# 19_-DDR4_260_PIN_CON.net
KiCad netlist of a schematic drawn in Altium Designer
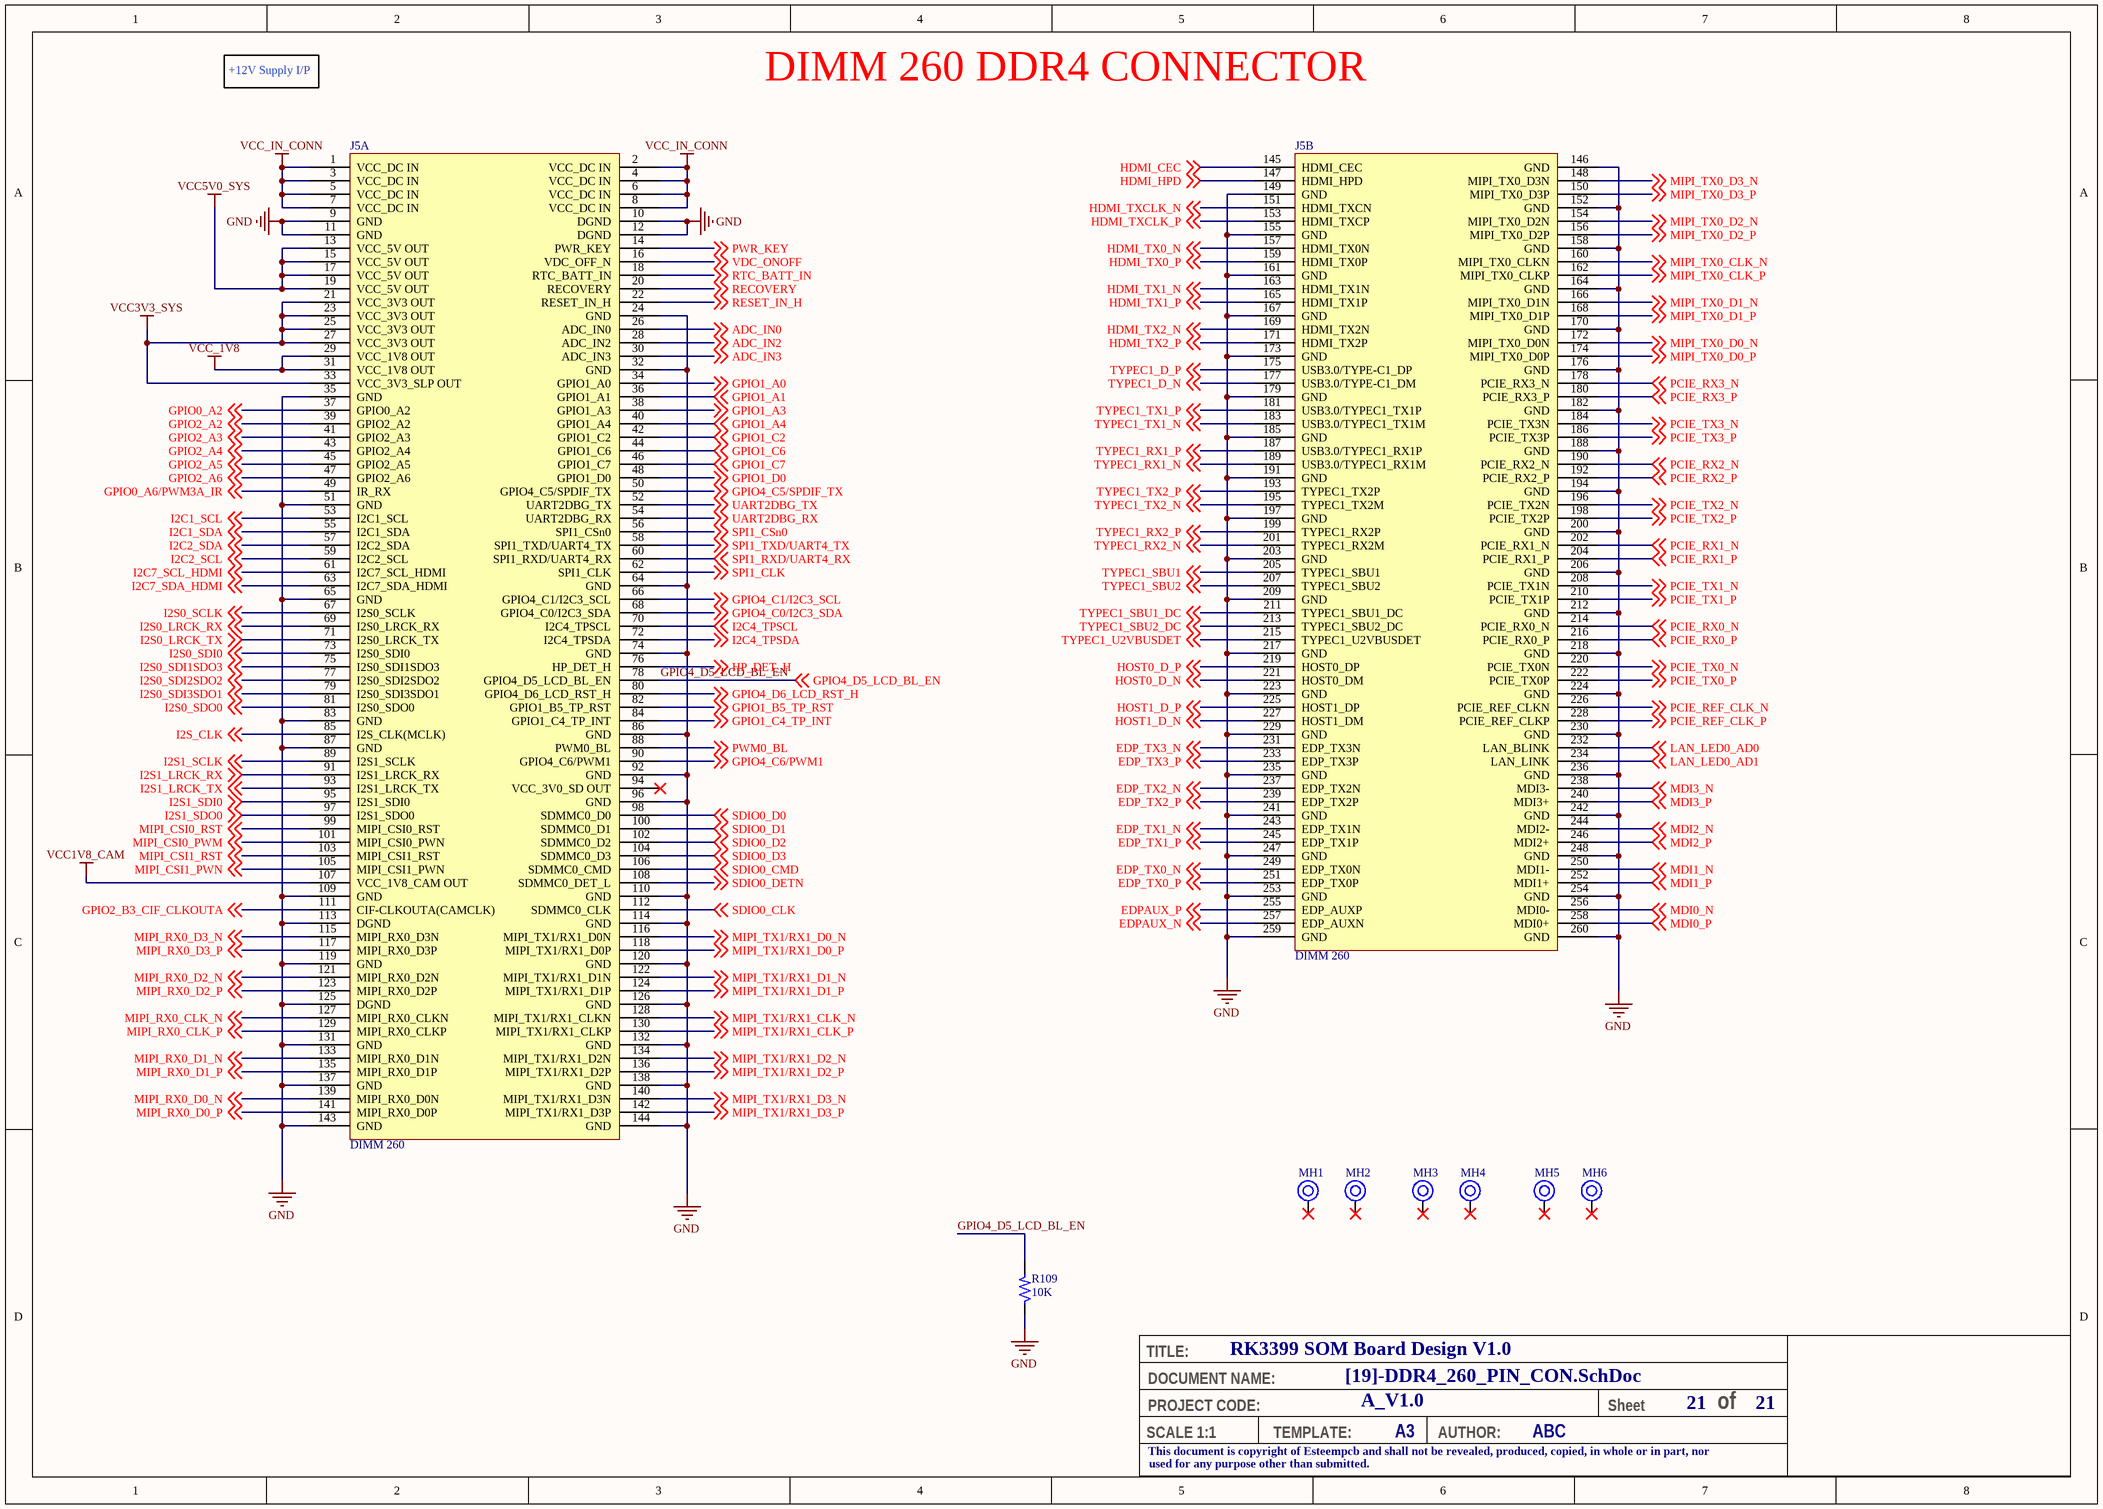
[diagram p0: [19]-DDR4_260_PIN_CON.SchDoc]

(export (version "E")
  (design (tool "Eeschema 10.0.6"))
  (components
    (comp (ref "J5")
      (value "DIMM 260")
      (footprint "DIMM260_DDR4")
      (description "Dimm 260 pin smd plating on pcb")
      (fields (field (name "MANUFACTURER") "NA"))
      (libsource (lib "RK3399 _Module_Schlib") (part "CON-DIMM_260-SMD"))
    )
    (comp (ref "MH1")
      (value "Mounting Hole")
      (footprint "SOM_Mounting")
      (fields (field (name "MANUFACTURER PART NUMBER") "NA"))
      (libsource (lib "EsteemPCB_SOM_Course_intlib") (part "MH_3.5H_6D"))
    )
    (comp (ref "MH2")
      (value "Mounting Hole")
      (footprint "SOM_Mounting")
      (fields (field (name "MANUFACTURER PART NUMBER") "NA"))
      (libsource (lib "EsteemPCB_SOM_Course_intlib") (part "MH_3.5H_6D"))
    )
    (comp (ref "MH3")
      (value "Mounting Hole")
      (footprint "SOM_Mounting")
      (fields (field (name "MANUFACTURER PART NUMBER") "NA"))
      (libsource (lib "EsteemPCB_SOM_Course_intlib") (part "MH_3.5H_6D"))
    )
    (comp (ref "MH4")
      (value "Mounting Hole")
      (footprint "SOM_Mounting")
      (fields (field (name "MANUFACTURER PART NUMBER") "NA"))
      (libsource (lib "EsteemPCB_SOM_Course_intlib") (part "MH_3.5H_6D"))
    )
    (comp (ref "MH5")
      (value "Mounting Hole")
      (footprint "SOM_Mounting")
      (fields (field (name "MANUFACTURER PART NUMBER") "NA"))
      (libsource (lib "EsteemPCB_SOM_Course_intlib") (part "MH_3.5H_6D"))
    )
    (comp (ref "MH6")
      (value "Mounting Hole")
      (footprint "SOM_Mounting")
      (fields (field (name "MANUFACTURER PART NUMBER") "NA"))
      (libsource (lib "EsteemPCB_SOM_Course_intlib") (part "MH_3.5H_6D"))
    )
    (comp (ref "R109")
      (value "10K")
      (footprint "RES_0402")
      (description "10 kOhms ±1% 0.1W, 1/10W Chip Resistor 0402 (1005 Metric) Anti-Sulfur Thin Film")
      (fields
        (field (name "MANUFACTURER") "Vishay Beyschlag/Draloric/BC Components")
        (field (name "MANUFACTURER PART NUMBER") "MCS04020C1002FE000")
      )
      (libsource (lib "RK3399 _Module_Schlib") (part "RES_10K-0.1W-1%-0402"))
    )
  )
  (nets
    (net (code "1") (name "ADC_IN0") (class "Default")
      (node (ref "J5") (pin "26") (pinfunction "ADC_IN0_26") (pintype "passive"))
    )
    (net (code "2") (name "ADC_IN2") (class "Default")
      (node (ref "J5") (pin "28") (pinfunction "ADC_IN2_28") (pintype "passive"))
    )
    (net (code "3") (name "ADC_IN3") (class "Default")
      (node (ref "J5") (pin "30") (pinfunction "ADC_IN3_30") (pintype "passive"))
    )
    (net (code "4") (name "EDPAUX_N") (class "Default")
      (node (ref "J5") (pin "257") (pinfunction "EDP_AUXN_257") (pintype "passive"))
    )
    (net (code "5") (name "EDPAUX_P") (class "Default")
      (node (ref "J5") (pin "255") (pinfunction "EDP_AUXP_255") (pintype "passive"))
    )
    (net (code "6") (name "EDP_TX0_N") (class "Default")
      (node (ref "J5") (pin "249") (pinfunction "EDP_TX0N_249") (pintype "passive"))
    )
    (net (code "7") (name "EDP_TX0_P") (class "Default")
      (node (ref "J5") (pin "251") (pinfunction "EDP_TX0P_251") (pintype "passive"))
    )
    (net (code "8") (name "EDP_TX1_N") (class "Default")
      (node (ref "J5") (pin "243") (pinfunction "EDP_TX1N_243") (pintype "passive"))
    )
    (net (code "9") (name "EDP_TX1_P") (class "Default")
      (node (ref "J5") (pin "245") (pinfunction "EDP_TX1P_245") (pintype "passive"))
    )
    (net (code "10") (name "EDP_TX2_N") (class "Default")
      (node (ref "J5") (pin "237") (pinfunction "EDP_TX2N_237") (pintype "passive"))
    )
    (net (code "11") (name "EDP_TX2_P") (class "Default")
      (node (ref "J5") (pin "239") (pinfunction "EDP_TX2P_239") (pintype "passive"))
    )
    (net (code "12") (name "EDP_TX3_N") (class "Default")
      (node (ref "J5") (pin "231") (pinfunction "EDP_TX3N_231") (pintype "passive"))
    )
    (net (code "13") (name "EDP_TX3_P") (class "Default")
      (node (ref "J5") (pin "233") (pinfunction "EDP_TX3P_233") (pintype "passive"))
    )
    (net (code "14") (name "GND") (class "Default")
      (node (ref "J5") (pin "10") (pinfunction "DGND_10") (pintype "passive"))
      (node (ref "J5") (pin "109") (pinfunction "GND_109") (pintype "passive"))
      (node (ref "J5") (pin "11") (pinfunction "GND_11") (pintype "passive"))
      (node (ref "J5") (pin "110") (pinfunction "GND_110") (pintype "passive"))
      (node (ref "J5") (pin "113") (pinfunction "DGND_113") (pintype "passive"))
      (node (ref "J5") (pin "114") (pinfunction "GND_114") (pintype "passive"))
      (node (ref "J5") (pin "119") (pinfunction "GND_119") (pintype "passive"))
      (node (ref "J5") (pin "12") (pinfunction "DGND_12") (pintype "passive"))
      (node (ref "J5") (pin "120") (pinfunction "GND_120") (pintype "passive"))
      (node (ref "J5") (pin "125") (pinfunction "DGND_125") (pintype "passive"))
      (node (ref "J5") (pin "126") (pinfunction "GND_126") (pintype "passive"))
      (node (ref "J5") (pin "131") (pinfunction "GND_131") (pintype "passive"))
      (node (ref "J5") (pin "132") (pinfunction "GND_132") (pintype "passive"))
      (node (ref "J5") (pin "137") (pinfunction "GND_137") (pintype "passive"))
      (node (ref "J5") (pin "138") (pinfunction "GND_138") (pintype "passive"))
      (node (ref "J5") (pin "143") (pinfunction "GND_143") (pintype "passive"))
      (node (ref "J5") (pin "144") (pinfunction "GND_144") (pintype "passive"))
      (node (ref "J5") (pin "146") (pinfunction "GND_146") (pintype "passive"))
      (node (ref "J5") (pin "149") (pinfunction "GND_149") (pintype "passive"))
      (node (ref "J5") (pin "152") (pinfunction "GND_152") (pintype "passive"))
      (node (ref "J5") (pin "155") (pinfunction "GND_155") (pintype "passive"))
      (node (ref "J5") (pin "158") (pinfunction "GND_158") (pintype "passive"))
      (node (ref "J5") (pin "161") (pinfunction "GND_161") (pintype "passive"))
      (node (ref "J5") (pin "164") (pinfunction "GND_164") (pintype "passive"))
      (node (ref "J5") (pin "167") (pinfunction "GND_167") (pintype "passive"))
      (node (ref "J5") (pin "170") (pinfunction "GND_170") (pintype "passive"))
      (node (ref "J5") (pin "173") (pinfunction "GND_173") (pintype "passive"))
      (node (ref "J5") (pin "176") (pinfunction "GND_176") (pintype "passive"))
      (node (ref "J5") (pin "179") (pinfunction "GND_179") (pintype "passive"))
      (node (ref "J5") (pin "182") (pinfunction "GND_182") (pintype "passive"))
      (node (ref "J5") (pin "185") (pinfunction "GND_185") (pintype "passive"))
      (node (ref "J5") (pin "188") (pinfunction "GND_188") (pintype "passive"))
      (node (ref "J5") (pin "191") (pinfunction "GND_191") (pintype "passive"))
      (node (ref "J5") (pin "194") (pinfunction "GND_194") (pintype "passive"))
      (node (ref "J5") (pin "197") (pinfunction "GND_197") (pintype "passive"))
      (node (ref "J5") (pin "200") (pinfunction "GND_200") (pintype "passive"))
      (node (ref "J5") (pin "203") (pinfunction "GND_203") (pintype "passive"))
      (node (ref "J5") (pin "206") (pinfunction "GND_206") (pintype "passive"))
      (node (ref "J5") (pin "209") (pinfunction "GND_209") (pintype "passive"))
      (node (ref "J5") (pin "212") (pinfunction "GND_212") (pintype "passive"))
      (node (ref "J5") (pin "217") (pinfunction "GND_217") (pintype "passive"))
      (node (ref "J5") (pin "218") (pinfunction "GND_218") (pintype "passive"))
      (node (ref "J5") (pin "223") (pinfunction "GND_223") (pintype "passive"))
      (node (ref "J5") (pin "224") (pinfunction "GND_224") (pintype "passive"))
      (node (ref "J5") (pin "229") (pinfunction "GND_229") (pintype "passive"))
      (node (ref "J5") (pin "230") (pinfunction "GND_230") (pintype "passive"))
      (node (ref "J5") (pin "235") (pinfunction "GND_235") (pintype "passive"))
      (node (ref "J5") (pin "236") (pinfunction "GND_236") (pintype "passive"))
      (node (ref "J5") (pin "24") (pinfunction "GND_24") (pintype "passive"))
      (node (ref "J5") (pin "241") (pinfunction "GND_241") (pintype "passive"))
      (node (ref "J5") (pin "242") (pinfunction "GND_242") (pintype "passive"))
      (node (ref "J5") (pin "247") (pinfunction "GND_247") (pintype "passive"))
      (node (ref "J5") (pin "248") (pinfunction "GND_248") (pintype "passive"))
      (node (ref "J5") (pin "253") (pinfunction "GND_253") (pintype "passive"))
      (node (ref "J5") (pin "254") (pinfunction "GND_254") (pintype "passive"))
      (node (ref "J5") (pin "259") (pinfunction "GND_259") (pintype "passive"))
      (node (ref "J5") (pin "260") (pinfunction "GND_260") (pintype "passive"))
      (node (ref "J5") (pin "32") (pinfunction "GND_32") (pintype "passive"))
      (node (ref "J5") (pin "35") (pinfunction "GND_35") (pintype "passive"))
      (node (ref "J5") (pin "51") (pinfunction "GND_51") (pintype "passive"))
      (node (ref "J5") (pin "64") (pinfunction "GND_64") (pintype "passive"))
      (node (ref "J5") (pin "65") (pinfunction "GND_65") (pintype "passive"))
      (node (ref "J5") (pin "74") (pinfunction "GND_74") (pintype "passive"))
      (node (ref "J5") (pin "83") (pinfunction "GND_83") (pintype "passive"))
      (node (ref "J5") (pin "86") (pinfunction "GND_86") (pintype "passive"))
      (node (ref "J5") (pin "87") (pinfunction "GND_87") (pintype "passive"))
      (node (ref "J5") (pin "9") (pinfunction "GND_9") (pintype "passive"))
      (node (ref "J5") (pin "92") (pinfunction "GND_92") (pintype "passive"))
      (node (ref "J5") (pin "96") (pinfunction "GND_96") (pintype "passive"))
      (node (ref "R109") (pin "1") (pinfunction "1_1") (pintype "passive"))
    )
    (net (code "15") (name "GPIO0_A2") (class "Default")
      (node (ref "J5") (pin "37") (pinfunction "GPIO0_A2_37") (pintype "passive"))
    )
    (net (code "16") (name "GPIO0_A6{slash}PWM3A_IR") (class "Default")
      (node (ref "J5") (pin "49") (pinfunction "IR_RX_49") (pintype "passive"))
    )
    (net (code "17") (name "GPIO1_A0") (class "Default")
      (node (ref "J5") (pin "34") (pinfunction "GPIO1_A0_34") (pintype "passive"))
    )
    (net (code "18") (name "GPIO1_A1") (class "Default")
      (node (ref "J5") (pin "36") (pinfunction "GPIO1_A1_36") (pintype "passive"))
    )
    (net (code "19") (name "GPIO1_A3") (class "Default")
      (node (ref "J5") (pin "38") (pinfunction "GPIO1_A3_38") (pintype "passive"))
    )
    (net (code "20") (name "GPIO1_A4") (class "Default")
      (node (ref "J5") (pin "40") (pinfunction "GPIO1_A4_40") (pintype "passive"))
    )
    (net (code "21") (name "GPIO1_B5_TP_RST") (class "Default")
      (node (ref "J5") (pin "82") (pinfunction "GPIO1_B5_TP_RST_82") (pintype "passive"))
    )
    (net (code "22") (name "GPIO1_C2") (class "Default")
      (node (ref "J5") (pin "42") (pinfunction "GPIO1_C2_42") (pintype "passive"))
    )
    (net (code "23") (name "GPIO1_C4_TP_INT") (class "Default")
      (node (ref "J5") (pin "84") (pinfunction "GPIO1_C4_TP_INT_84") (pintype "passive"))
    )
    (net (code "24") (name "GPIO1_C6") (class "Default")
      (node (ref "J5") (pin "44") (pinfunction "GPIO1_C6_44") (pintype "passive"))
    )
    (net (code "25") (name "GPIO1_C7") (class "Default")
      (node (ref "J5") (pin "46") (pinfunction "GPIO1_C7_46") (pintype "passive"))
    )
    (net (code "26") (name "GPIO1_D0") (class "Default")
      (node (ref "J5") (pin "48") (pinfunction "GPIO1_D0_48") (pintype "passive"))
    )
    (net (code "27") (name "GPIO2_A2") (class "Default")
      (node (ref "J5") (pin "39") (pinfunction "GPIO2_A2_39") (pintype "passive"))
    )
    (net (code "28") (name "GPIO2_A3") (class "Default")
      (node (ref "J5") (pin "41") (pinfunction "GPIO2_A3_41") (pintype "passive"))
    )
    (net (code "29") (name "GPIO2_A4") (class "Default")
      (node (ref "J5") (pin "43") (pinfunction "GPIO2_A4_43") (pintype "passive"))
    )
    (net (code "30") (name "GPIO2_A5") (class "Default")
      (node (ref "J5") (pin "45") (pinfunction "GPIO2_A5_45") (pintype "passive"))
    )
    (net (code "31") (name "GPIO2_A6") (class "Default")
      (node (ref "J5") (pin "47") (pinfunction "GPIO2_A6_47") (pintype "passive"))
    )
    (net (code "32") (name "GPIO2_B3_CIF_CLKOUTA") (class "Default")
      (node (ref "J5") (pin "111") (pinfunction "CIF-CLKOUTA(CAMCLK)_111") (pintype "passive"))
    )
    (net (code "33") (name "GPIO4_C0{slash}I2C3_SDA") (class "Default")
      (node (ref "J5") (pin "68") (pinfunction "GPIO4_C0/I2C3_SDA_68") (pintype "passive"))
    )
    (net (code "34") (name "GPIO4_C1{slash}I2C3_SCL") (class "Default")
      (node (ref "J5") (pin "66") (pinfunction "GPIO4_C1/I2C3_SCL_66") (pintype "passive"))
    )
    (net (code "35") (name "GPIO4_C5{slash}SPDIF_TX") (class "Default")
      (node (ref "J5") (pin "50") (pinfunction "GPIO4_C5/SPDIF_TX_50") (pintype "passive"))
    )
    (net (code "36") (name "GPIO4_C6{slash}PWM1") (class "Default")
      (node (ref "J5") (pin "90") (pinfunction "GPIO4_C6/PWM1_90") (pintype "passive"))
    )
    (net (code "37") (name "GPIO4_D5_LCD_BL_EN") (class "Default")
      (node (ref "J5") (pin "78") (pinfunction "GPIO4_D5_LCD_BL_EN_78") (pintype "passive"))
      (node (ref "R109") (pin "2") (pinfunction "2_2") (pintype "passive"))
    )
    (net (code "38") (name "GPIO4_D6_LCD_RST_H") (class "Default")
      (node (ref "J5") (pin "80") (pinfunction "GPIO4_D6_LCD_RST_H_80") (pintype "passive"))
    )
    (net (code "39") (name "HDMI_CEC") (class "Default")
      (node (ref "J5") (pin "145") (pinfunction "HDMI_CEC_145") (pintype "passive"))
    )
    (net (code "40") (name "HDMI_HPD") (class "Default")
      (node (ref "J5") (pin "147") (pinfunction "HDMI_HPD_147") (pintype "passive"))
    )
    (net (code "41") (name "HDMI_TX0_N") (class "Default")
      (node (ref "J5") (pin "157") (pinfunction "HDMI_TX0N_157") (pintype "passive"))
    )
    (net (code "42") (name "HDMI_TX0_P") (class "Default")
      (node (ref "J5") (pin "159") (pinfunction "HDMI_TX0P_159") (pintype "passive"))
    )
    (net (code "43") (name "HDMI_TX1_N") (class "Default")
      (node (ref "J5") (pin "163") (pinfunction "HDMI_TX1N_163") (pintype "passive"))
    )
    (net (code "44") (name "HDMI_TX1_P") (class "Default")
      (node (ref "J5") (pin "165") (pinfunction "HDMI_TX1P_165") (pintype "passive"))
    )
    (net (code "45") (name "HDMI_TX2_N") (class "Default")
      (node (ref "J5") (pin "169") (pinfunction "HDMI_TX2N_169") (pintype "passive"))
    )
    (net (code "46") (name "HDMI_TX2_P") (class "Default")
      (node (ref "J5") (pin "171") (pinfunction "HDMI_TX2P_171") (pintype "passive"))
    )
    (net (code "47") (name "HDMI_TXCLK_N") (class "Default")
      (node (ref "J5") (pin "151") (pinfunction "HDMI_TXCN_151") (pintype "passive"))
    )
    (net (code "48") (name "HDMI_TXCLK_P") (class "Default")
      (node (ref "J5") (pin "153") (pinfunction "HDMI_TXCP_153") (pintype "passive"))
    )
    (net (code "49") (name "HOST0_D_N") (class "Default")
      (node (ref "J5") (pin "221") (pinfunction "HOST0_DM_221") (pintype "passive"))
    )
    (net (code "50") (name "HOST0_D_P") (class "Default")
      (node (ref "J5") (pin "219") (pinfunction "HOST0_DP_219") (pintype "passive"))
    )
    (net (code "51") (name "HOST1_D_N") (class "Default")
      (node (ref "J5") (pin "227") (pinfunction "HOST1_DM_227") (pintype "passive"))
    )
    (net (code "52") (name "HOST1_D_P") (class "Default")
      (node (ref "J5") (pin "225") (pinfunction "HOST1_DP_225") (pintype "passive"))
    )
    (net (code "53") (name "HP_DET_H") (class "Default")
      (node (ref "J5") (pin "76") (pinfunction "HP_DET_H_76") (pintype "passive"))
    )
    (net (code "54") (name "I2C1_SCL") (class "Default")
      (node (ref "J5") (pin "53") (pinfunction "I2C1_SCL_53") (pintype "passive"))
    )
    (net (code "55") (name "I2C1_SDA") (class "Default")
      (node (ref "J5") (pin "55") (pinfunction "I2C1_SDA_55") (pintype "passive"))
    )
    (net (code "56") (name "I2C2_SCL") (class "Default")
      (node (ref "J5") (pin "59") (pinfunction "I2C2_SCL_59") (pintype "passive"))
    )
    (net (code "57") (name "I2C2_SDA") (class "Default")
      (node (ref "J5") (pin "57") (pinfunction "I2C2_SDA_57") (pintype "passive"))
    )
    (net (code "58") (name "I2C4_TPSCL") (class "Default")
      (node (ref "J5") (pin "70") (pinfunction "I2C4_TPSCL_70") (pintype "passive"))
    )
    (net (code "59") (name "I2C4_TPSDA") (class "Default")
      (node (ref "J5") (pin "72") (pinfunction "I2C4_TPSDA_72") (pintype "passive"))
    )
    (net (code "60") (name "I2C7_SCL_HDMI") (class "Default")
      (node (ref "J5") (pin "61") (pinfunction "I2C7_SCL_HDMI_61") (pintype "passive"))
    )
    (net (code "61") (name "I2C7_SDA_HDMI") (class "Default")
      (node (ref "J5") (pin "63") (pinfunction "I2C7_SDA_HDMI_63") (pintype "passive"))
    )
    (net (code "62") (name "I2S0_LRCK_RX") (class "Default")
      (node (ref "J5") (pin "69") (pinfunction "I2S0_LRCK_RX_69") (pintype "passive"))
    )
    (net (code "63") (name "I2S0_LRCK_TX") (class "Default")
      (node (ref "J5") (pin "71") (pinfunction "I2S0_LRCK_TX_71") (pintype "passive"))
    )
    (net (code "64") (name "I2S0_SCLK") (class "Default")
      (node (ref "J5") (pin "67") (pinfunction "I2S0_SCLK_67") (pintype "passive"))
    )
    (net (code "65") (name "I2S0_SDI0") (class "Default")
      (node (ref "J5") (pin "73") (pinfunction "I2S0_SDI0_73") (pintype "passive"))
    )
    (net (code "66") (name "I2S0_SDI1SDO3") (class "Default")
      (node (ref "J5") (pin "75") (pinfunction "I2S0_SDI1SDO3_75") (pintype "passive"))
    )
    (net (code "67") (name "I2S0_SDI2SDO2") (class "Default")
      (node (ref "J5") (pin "77") (pinfunction "I2S0_SDI2SDO2_77") (pintype "passive"))
    )
    (net (code "68") (name "I2S0_SDI3SDO1") (class "Default")
      (node (ref "J5") (pin "79") (pinfunction "I2S0_SDI3SDO1_79") (pintype "passive"))
    )
    (net (code "69") (name "I2S0_SDO0") (class "Default")
      (node (ref "J5") (pin "81") (pinfunction "I2S0_SDO0_81") (pintype "passive"))
    )
    (net (code "70") (name "I2S1_LRCK_RX") (class "Default")
      (node (ref "J5") (pin "91") (pinfunction "I2S1_LRCK_RX_91") (pintype "passive"))
    )
    (net (code "71") (name "I2S1_LRCK_TX") (class "Default")
      (node (ref "J5") (pin "93") (pinfunction "I2S1_LRCK_TX_93") (pintype "passive"))
    )
    (net (code "72") (name "I2S1_SCLK") (class "Default")
      (node (ref "J5") (pin "89") (pinfunction "I2S1_SCLK_89") (pintype "passive"))
    )
    (net (code "73") (name "I2S1_SDI0") (class "Default")
      (node (ref "J5") (pin "95") (pinfunction "I2S1_SDI0_95") (pintype "passive"))
    )
    (net (code "74") (name "I2S1_SDO0") (class "Default")
      (node (ref "J5") (pin "97") (pinfunction "I2S1_SDO0_97") (pintype "passive"))
    )
    (net (code "75") (name "I2S_CLK") (class "Default")
      (node (ref "J5") (pin "85") (pinfunction "I2S_CLK(MCLK)_85") (pintype "passive"))
    )
    (net (code "76") (name "LAN_LED0_AD0") (class "Default")
      (node (ref "J5") (pin "232") (pinfunction "LAN_BLINK_232") (pintype "passive"))
    )
    (net (code "77") (name "LAN_LED0_AD1") (class "Default")
      (node (ref "J5") (pin "234") (pinfunction "LAN_LINK_234") (pintype "passive"))
    )
    (net (code "78") (name "MDI0_N") (class "Default")
      (node (ref "J5") (pin "256") (pinfunction "MDI0-_256") (pintype "passive"))
    )
    (net (code "79") (name "MDI0_P") (class "Default")
      (node (ref "J5") (pin "258") (pinfunction "MDI0+_258") (pintype "passive"))
    )
    (net (code "80") (name "MDI1_N") (class "Default")
      (node (ref "J5") (pin "250") (pinfunction "MDI1-_250") (pintype "passive"))
    )
    (net (code "81") (name "MDI1_P") (class "Default")
      (node (ref "J5") (pin "252") (pinfunction "MDI1+_252") (pintype "passive"))
    )
    (net (code "82") (name "MDI2_N") (class "Default")
      (node (ref "J5") (pin "244") (pinfunction "MDI2-_244") (pintype "passive"))
    )
    (net (code "83") (name "MDI2_P") (class "Default")
      (node (ref "J5") (pin "246") (pinfunction "MDI2+_246") (pintype "passive"))
    )
    (net (code "84") (name "MDI3_N") (class "Default")
      (node (ref "J5") (pin "238") (pinfunction "MDI3-_238") (pintype "passive"))
    )
    (net (code "85") (name "MDI3_P") (class "Default")
      (node (ref "J5") (pin "240") (pinfunction "MDI3+_240") (pintype "passive"))
    )
    (net (code "86") (name "MIPI_CSI0_PWM") (class "Default")
      (node (ref "J5") (pin "101") (pinfunction "MIPI_CSI0_PWN_101") (pintype "passive"))
    )
    (net (code "87") (name "MIPI_CSI0_RST") (class "Default")
      (node (ref "J5") (pin "99") (pinfunction "MIPI_CSI0_RST_99") (pintype "passive"))
    )
    (net (code "88") (name "MIPI_CSI1_PWN") (class "Default")
      (node (ref "J5") (pin "105") (pinfunction "MIPI_CSI1_PWN_105") (pintype "passive"))
    )
    (net (code "89") (name "MIPI_CSI1_RST") (class "Default")
      (node (ref "J5") (pin "103") (pinfunction "MIPI_CSI1_RST_103") (pintype "passive"))
    )
    (net (code "90") (name "MIPI_RX0_CLK_N") (class "Default")
      (node (ref "J5") (pin "127") (pinfunction "MIPI_RX0_CLKN_127") (pintype "passive"))
    )
    (net (code "91") (name "MIPI_RX0_CLK_P") (class "Default")
      (node (ref "J5") (pin "129") (pinfunction "MIPI_RX0_CLKP_129") (pintype "passive"))
    )
    (net (code "92") (name "MIPI_RX0_D0_N") (class "Default")
      (node (ref "J5") (pin "139") (pinfunction "MIPI_RX0_D0N_139") (pintype "passive"))
    )
    (net (code "93") (name "MIPI_RX0_D0_P") (class "Default")
      (node (ref "J5") (pin "141") (pinfunction "MIPI_RX0_D0P_141") (pintype "passive"))
    )
    (net (code "94") (name "MIPI_RX0_D1_N") (class "Default")
      (node (ref "J5") (pin "133") (pinfunction "MIPI_RX0_D1N_133") (pintype "passive"))
    )
    (net (code "95") (name "MIPI_RX0_D1_P") (class "Default")
      (node (ref "J5") (pin "135") (pinfunction "MIPI_RX0_D1P_135") (pintype "passive"))
    )
    (net (code "96") (name "MIPI_RX0_D2_N") (class "Default")
      (node (ref "J5") (pin "121") (pinfunction "MIPI_RX0_D2N_121") (pintype "passive"))
    )
    (net (code "97") (name "MIPI_RX0_D2_P") (class "Default")
      (node (ref "J5") (pin "123") (pinfunction "MIPI_RX0_D2P_123") (pintype "passive"))
    )
    (net (code "98") (name "MIPI_RX0_D3_N") (class "Default")
      (node (ref "J5") (pin "115") (pinfunction "MIPI_RX0_D3N_115") (pintype "passive"))
    )
    (net (code "99") (name "MIPI_RX0_D3_P") (class "Default")
      (node (ref "J5") (pin "117") (pinfunction "MIPI_RX0_D3P_117") (pintype "passive"))
    )
    (net (code "100") (name "MIPI_TX0_CLK_N") (class "Default")
      (node (ref "J5") (pin "160") (pinfunction "MIPI_TX0_CLKN_160") (pintype "passive"))
    )
    (net (code "101") (name "MIPI_TX0_CLK_P") (class "Default")
      (node (ref "J5") (pin "162") (pinfunction "MIPI_TX0_CLKP_162") (pintype "passive"))
    )
    (net (code "102") (name "MIPI_TX0_D0_N") (class "Default")
      (node (ref "J5") (pin "172") (pinfunction "MIPI_TX0_D0N_172") (pintype "passive"))
    )
    (net (code "103") (name "MIPI_TX0_D0_P") (class "Default")
      (node (ref "J5") (pin "174") (pinfunction "MIPI_TX0_D0P_174") (pintype "passive"))
    )
    (net (code "104") (name "MIPI_TX0_D1_N") (class "Default")
      (node (ref "J5") (pin "166") (pinfunction "MIPI_TX0_D1N_166") (pintype "passive"))
    )
    (net (code "105") (name "MIPI_TX0_D1_P") (class "Default")
      (node (ref "J5") (pin "168") (pinfunction "MIPI_TX0_D1P_168") (pintype "passive"))
    )
    (net (code "106") (name "MIPI_TX0_D2_N") (class "Default")
      (node (ref "J5") (pin "154") (pinfunction "MIPI_TX0_D2N_154") (pintype "passive"))
    )
    (net (code "107") (name "MIPI_TX0_D2_P") (class "Default")
      (node (ref "J5") (pin "156") (pinfunction "MIPI_TX0_D2P_156") (pintype "passive"))
    )
    (net (code "108") (name "MIPI_TX0_D3_N") (class "Default")
      (node (ref "J5") (pin "148") (pinfunction "MIPI_TX0_D3N_148") (pintype "passive"))
    )
    (net (code "109") (name "MIPI_TX0_D3_P") (class "Default")
      (node (ref "J5") (pin "150") (pinfunction "MIPI_TX0_D3P_150") (pintype "passive"))
    )
    (net (code "110") (name "MIPI_TX1{slash}RX1_CLK_N") (class "Default")
      (node (ref "J5") (pin "128") (pinfunction "MIPI_TX1/RX1_CLKN_128") (pintype "passive"))
    )
    (net (code "111") (name "MIPI_TX1{slash}RX1_CLK_P") (class "Default")
      (node (ref "J5") (pin "130") (pinfunction "MIPI_TX1/RX1_CLKP_130") (pintype "passive"))
    )
    (net (code "112") (name "MIPI_TX1{slash}RX1_D0_N") (class "Default")
      (node (ref "J5") (pin "116") (pinfunction "MIPI_TX1/RX1_D0N_116") (pintype "passive"))
    )
    (net (code "113") (name "MIPI_TX1{slash}RX1_D0_P") (class "Default")
      (node (ref "J5") (pin "118") (pinfunction "MIPI_TX1/RX1_D0P_118") (pintype "passive"))
    )
    (net (code "114") (name "MIPI_TX1{slash}RX1_D1_N") (class "Default")
      (node (ref "J5") (pin "122") (pinfunction "MIPI_TX1/RX1_D1N_122") (pintype "passive"))
    )
    (net (code "115") (name "MIPI_TX1{slash}RX1_D1_P") (class "Default")
      (node (ref "J5") (pin "124") (pinfunction "MIPI_TX1/RX1_D1P_124") (pintype "passive"))
    )
    (net (code "116") (name "MIPI_TX1{slash}RX1_D2_N") (class "Default")
      (node (ref "J5") (pin "134") (pinfunction "MIPI_TX1/RX1_D2N_134") (pintype "passive"))
    )
    (net (code "117") (name "MIPI_TX1{slash}RX1_D2_P") (class "Default")
      (node (ref "J5") (pin "136") (pinfunction "MIPI_TX1/RX1_D2P_136") (pintype "passive"))
    )
    (net (code "118") (name "MIPI_TX1{slash}RX1_D3_N") (class "Default")
      (node (ref "J5") (pin "140") (pinfunction "MIPI_TX1/RX1_D3N_140") (pintype "passive"))
    )
    (net (code "119") (name "MIPI_TX1{slash}RX1_D3_P") (class "Default")
      (node (ref "J5") (pin "142") (pinfunction "MIPI_TX1/RX1_D3P_142") (pintype "passive"))
    )
    (net (code "120") (name "PCIE_REF_CLK_N") (class "Default")
      (node (ref "J5") (pin "226") (pinfunction "PCIE_REF_CLKN_226") (pintype "passive"))
    )
    (net (code "121") (name "PCIE_REF_CLK_P") (class "Default")
      (node (ref "J5") (pin "228") (pinfunction "PCIE_REF_CLKP_228") (pintype "passive"))
    )
    (net (code "122") (name "PCIE_RX0_N") (class "Default")
      (node (ref "J5") (pin "214") (pinfunction "PCIE_RX0_N_214") (pintype "passive"))
    )
    (net (code "123") (name "PCIE_RX0_P") (class "Default")
      (node (ref "J5") (pin "216") (pinfunction "PCIE_RX0_P_216") (pintype "passive"))
    )
    (net (code "124") (name "PCIE_RX1_N") (class "Default")
      (node (ref "J5") (pin "202") (pinfunction "PCIE_RX1_N_202") (pintype "passive"))
    )
    (net (code "125") (name "PCIE_RX1_P") (class "Default")
      (node (ref "J5") (pin "204") (pinfunction "PCIE_RX1_P_204") (pintype "passive"))
    )
    (net (code "126") (name "PCIE_RX2_N") (class "Default")
      (node (ref "J5") (pin "190") (pinfunction "PCIE_RX2_N_190") (pintype "passive"))
    )
    (net (code "127") (name "PCIE_RX2_P") (class "Default")
      (node (ref "J5") (pin "192") (pinfunction "PCIE_RX2_P_192") (pintype "passive"))
    )
    (net (code "128") (name "PCIE_RX3_N") (class "Default")
      (node (ref "J5") (pin "178") (pinfunction "PCIE_RX3_N_178") (pintype "passive"))
    )
    (net (code "129") (name "PCIE_RX3_P") (class "Default")
      (node (ref "J5") (pin "180") (pinfunction "PCIE_RX3_P_180") (pintype "passive"))
    )
    (net (code "130") (name "PCIE_TX0_N") (class "Default")
      (node (ref "J5") (pin "220") (pinfunction "PCIE_TX0N_220") (pintype "passive"))
    )
    (net (code "131") (name "PCIE_TX0_P") (class "Default")
      (node (ref "J5") (pin "222") (pinfunction "PCIE_TX0P_222") (pintype "passive"))
    )
    (net (code "132") (name "PCIE_TX1_N") (class "Default")
      (node (ref "J5") (pin "208") (pinfunction "PCIE_TX1N_208") (pintype "passive"))
    )
    (net (code "133") (name "PCIE_TX1_P") (class "Default")
      (node (ref "J5") (pin "210") (pinfunction "PCIE_TX1P_210") (pintype "passive"))
    )
    (net (code "134") (name "PCIE_TX2_N") (class "Default")
      (node (ref "J5") (pin "196") (pinfunction "PCIE_TX2N_196") (pintype "passive"))
    )
    (net (code "135") (name "PCIE_TX2_P") (class "Default")
      (node (ref "J5") (pin "198") (pinfunction "PCIE_TX2P_198") (pintype "passive"))
    )
    (net (code "136") (name "PCIE_TX3_N") (class "Default")
      (node (ref "J5") (pin "184") (pinfunction "PCIE_TX3N_184") (pintype "passive"))
    )
    (net (code "137") (name "PCIE_TX3_P") (class "Default")
      (node (ref "J5") (pin "186") (pinfunction "PCIE_TX3P_186") (pintype "passive"))
    )
    (net (code "138") (name "PWM0_BL") (class "Default")
      (node (ref "J5") (pin "88") (pinfunction "PWM0_BL_88") (pintype "passive"))
    )
    (net (code "139") (name "PWR_KEY") (class "Default")
      (node (ref "J5") (pin "14") (pinfunction "PWR_KEY_14") (pintype "passive"))
    )
    (net (code "140") (name "RECOVERY") (class "Default")
      (node (ref "J5") (pin "20") (pinfunction "RECOVERY_20") (pintype "passive"))
    )
    (net (code "141") (name "RESET_IN_H") (class "Default")
      (node (ref "J5") (pin "22") (pinfunction "RESET_IN_H_22") (pintype "passive"))
    )
    (net (code "142") (name "RTC_BATT_IN") (class "Default")
      (node (ref "J5") (pin "18") (pinfunction "RTC_BATT_IN_18") (pintype "passive"))
    )
    (net (code "143") (name "SDIO0_CLK") (class "Default")
      (node (ref "J5") (pin "112") (pinfunction "SDMMC0_CLK_112") (pintype "passive"))
    )
    (net (code "144") (name "SDIO0_CMD") (class "Default")
      (node (ref "J5") (pin "106") (pinfunction "SDMMC0_CMD_106") (pintype "passive"))
    )
    (net (code "145") (name "SDIO0_D0") (class "Default")
      (node (ref "J5") (pin "98") (pinfunction "SDMMC0_D0_98") (pintype "passive"))
    )
    (net (code "146") (name "SDIO0_D1") (class "Default")
      (node (ref "J5") (pin "100") (pinfunction "SDMMC0_D1_100") (pintype "passive"))
    )
    (net (code "147") (name "SDIO0_D2") (class "Default")
      (node (ref "J5") (pin "102") (pinfunction "SDMMC0_D2_102") (pintype "passive"))
    )
    (net (code "148") (name "SDIO0_D3") (class "Default")
      (node (ref "J5") (pin "104") (pinfunction "SDMMC0_D3_104") (pintype "passive"))
    )
    (net (code "149") (name "SDIO0_DETN") (class "Default")
      (node (ref "J5") (pin "108") (pinfunction "SDMMC0_DET_L_108") (pintype "passive"))
    )
    (net (code "150") (name "SPI1_CLK") (class "Default")
      (node (ref "J5") (pin "62") (pinfunction "SPI1_CLK_62") (pintype "passive"))
    )
    (net (code "151") (name "SPI1_CSn0") (class "Default")
      (node (ref "J5") (pin "56") (pinfunction "SPI1_CSn0_56") (pintype "passive"))
    )
    (net (code "152") (name "SPI1_RXD{slash}UART4_RX") (class "Default")
      (node (ref "J5") (pin "60") (pinfunction "SPI1_RXD/UART4_RX_60") (pintype "passive"))
    )
    (net (code "153") (name "SPI1_TXD{slash}UART4_TX") (class "Default")
      (node (ref "J5") (pin "58") (pinfunction "SPI1_TXD/UART4_TX_58") (pintype "passive"))
    )
    (net (code "154") (name "TYPEC1_D_N") (class "Default")
      (node (ref "J5") (pin "177") (pinfunction "USB3.0/TYPE-C1_DM_177") (pintype "passive"))
    )
    (net (code "155") (name "TYPEC1_D_P") (class "Default")
      (node (ref "J5") (pin "175") (pinfunction "USB3.0/TYPE-C1_DP_175") (pintype "passive"))
    )
    (net (code "156") (name "TYPEC1_RX1_N") (class "Default")
      (node (ref "J5") (pin "189") (pinfunction "USB3.0/TYPEC1_RX1M_189") (pintype "passive"))
    )
    (net (code "157") (name "TYPEC1_RX1_P") (class "Default")
      (node (ref "J5") (pin "187") (pinfunction "USB3.0/TYPEC1_RX1P_187") (pintype "passive"))
    )
    (net (code "158") (name "TYPEC1_RX2_N") (class "Default")
      (node (ref "J5") (pin "201") (pinfunction "TYPEC1_RX2M_201") (pintype "passive"))
    )
    (net (code "159") (name "TYPEC1_RX2_P") (class "Default")
      (node (ref "J5") (pin "199") (pinfunction "TYPEC1_RX2P_199") (pintype "passive"))
    )
    (net (code "160") (name "TYPEC1_SBU1") (class "Default")
      (node (ref "J5") (pin "205") (pinfunction "TYPEC1_SBU1_205") (pintype "passive"))
    )
    (net (code "161") (name "TYPEC1_SBU1_DC") (class "Default")
      (node (ref "J5") (pin "211") (pinfunction "TYPEC1_SBU1_DC_211") (pintype "passive"))
    )
    (net (code "162") (name "TYPEC1_SBU2") (class "Default")
      (node (ref "J5") (pin "207") (pinfunction "TYPEC1_SBU2_207") (pintype "passive"))
    )
    (net (code "163") (name "TYPEC1_SBU2_DC") (class "Default")
      (node (ref "J5") (pin "213") (pinfunction "TYPEC1_SBU2_DC_213") (pintype "passive"))
    )
    (net (code "164") (name "TYPEC1_TX1_N") (class "Default")
      (node (ref "J5") (pin "183") (pinfunction "USB3.0/TYPEC1_TX1M_183") (pintype "passive"))
    )
    (net (code "165") (name "TYPEC1_TX1_P") (class "Default")
      (node (ref "J5") (pin "181") (pinfunction "USB3.0/TYPEC1_TX1P_181") (pintype "passive"))
    )
    (net (code "166") (name "TYPEC1_TX2_N") (class "Default")
      (node (ref "J5") (pin "195") (pinfunction "TYPEC1_TX2M_195") (pintype "passive"))
    )
    (net (code "167") (name "TYPEC1_TX2_P") (class "Default")
      (node (ref "J5") (pin "193") (pinfunction "TYPEC1_TX2P_193") (pintype "passive"))
    )
    (net (code "168") (name "TYPEC1_U2VBUSDET") (class "Default")
      (node (ref "J5") (pin "215") (pinfunction "TYPEC1_U2VBUSDET_215") (pintype "passive"))
    )
    (net (code "169") (name "UART2DBG_RX") (class "Default")
      (node (ref "J5") (pin "54") (pinfunction "UART2DBG_RX_54") (pintype "passive"))
    )
    (net (code "170") (name "UART2DBG_TX") (class "Default")
      (node (ref "J5") (pin "52") (pinfunction "UART2DBG_TX_52") (pintype "passive"))
    )
    (net (code "171") (name "VCC1V8_CAM") (class "Default")
      (node (ref "J5") (pin "107") (pinfunction "VCC_1V8_CAM_OUT_107") (pintype "passive"))
    )
    (net (code "172") (name "VCC3V3_SYS") (class "Default")
      (node (ref "J5") (pin "21") (pinfunction "VCC_3V3_OUT_21") (pintype "passive"))
      (node (ref "J5") (pin "23") (pinfunction "VCC_3V3_OUT_23") (pintype "passive"))
      (node (ref "J5") (pin "25") (pinfunction "VCC_3V3_OUT_25") (pintype "passive"))
      (node (ref "J5") (pin "27") (pinfunction "VCC_3V3_OUT_27") (pintype "passive"))
      (node (ref "J5") (pin "33") (pinfunction "VCC_3V3_SLP_OUT_33") (pintype "passive"))
    )
    (net (code "173") (name "VCC5V0_SYS") (class "Default")
      (node (ref "J5") (pin "13") (pinfunction "VCC_5V_OUT_13") (pintype "passive"))
      (node (ref "J5") (pin "15") (pinfunction "VCC_5V_OUT_15") (pintype "passive"))
      (node (ref "J5") (pin "17") (pinfunction "VCC_5V_OUT_17") (pintype "passive"))
      (node (ref "J5") (pin "19") (pinfunction "VCC_5V_OUT_19") (pintype "passive"))
    )
    (net (code "174") (name "VCC_1V8") (class "Default")
      (node (ref "J5") (pin "29") (pinfunction "VCC_1V8_OUT_29") (pintype "passive"))
      (node (ref "J5") (pin "31") (pinfunction "VCC_1V8_OUT_31") (pintype "passive"))
    )
    (net (code "175") (name "VCC_IN_CONN") (class "Default")
      (node (ref "J5") (pin "1") (pinfunction "VCC_DC_IN_1") (pintype "passive"))
      (node (ref "J5") (pin "2") (pinfunction "VCC_DC_IN_2") (pintype "passive"))
      (node (ref "J5") (pin "3") (pinfunction "VCC_DC_IN_3") (pintype "passive"))
      (node (ref "J5") (pin "4") (pinfunction "VCC_DC_IN_4") (pintype "passive"))
      (node (ref "J5") (pin "5") (pinfunction "VCC_DC_IN_5") (pintype "passive"))
      (node (ref "J5") (pin "6") (pinfunction "VCC_DC_IN_6") (pintype "passive"))
      (node (ref "J5") (pin "7") (pinfunction "VCC_DC_IN_7") (pintype "passive"))
      (node (ref "J5") (pin "8") (pinfunction "VCC_DC_IN_8") (pintype "passive"))
    )
    (net (code "176") (name "VDC_ONOFF") (class "Default")
      (node (ref "J5") (pin "16") (pinfunction "VDC_OFF_N_16") (pintype "passive"))
    )
    (net (code "177") (name "unconnected-(J5A-VCC_3V0_SD_OUT-Pad94)") (class "Default")
      (node (ref "J5") (pin "94") (pinfunction "VCC_3V0_SD_OUT_94") (pintype "passive+no_connect"))
    )
    (net (code "178") (name "unconnected-(MH1-Pad1)") (class "Default")
      (node (ref "MH1") (pin "1") (pinfunction "1_1") (pintype "passive+no_connect"))
    )
    (net (code "179") (name "unconnected-(MH2-Pad1)") (class "Default")
      (node (ref "MH2") (pin "1") (pinfunction "1_1") (pintype "passive+no_connect"))
    )
    (net (code "180") (name "unconnected-(MH3-Pad1)") (class "Default")
      (node (ref "MH3") (pin "1") (pinfunction "1_1") (pintype "passive+no_connect"))
    )
    (net (code "181") (name "unconnected-(MH4-Pad1)") (class "Default")
      (node (ref "MH4") (pin "1") (pinfunction "1_1") (pintype "passive+no_connect"))
    )
    (net (code "182") (name "unconnected-(MH5-Pad1)") (class "Default")
      (node (ref "MH5") (pin "1") (pinfunction "1_1") (pintype "passive+no_connect"))
    )
    (net (code "183") (name "unconnected-(MH6-Pad1)") (class "Default")
      (node (ref "MH6") (pin "1") (pinfunction "1_1") (pintype "passive+no_connect"))
    )
  )
)
